# GateCircuit.net
KiCad netlist of a schematic drawn in Altium Designer
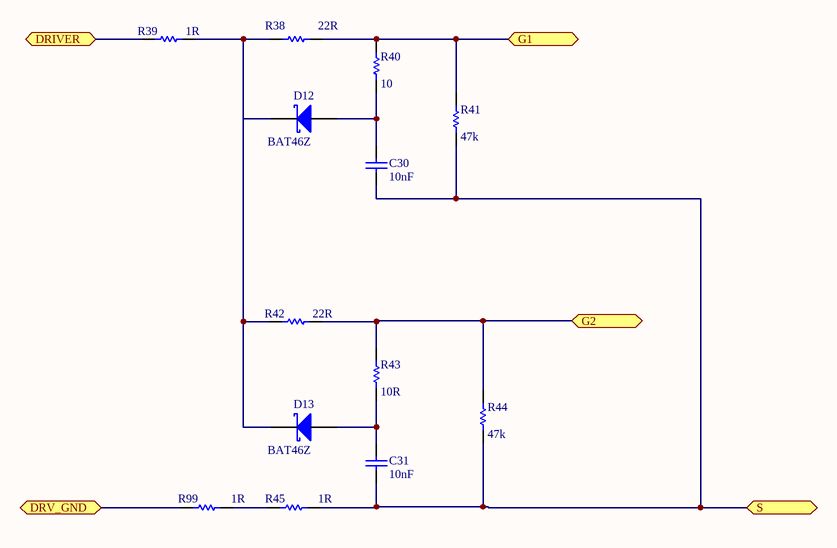
[diagram p0: GateCircuit.SchDoc]

(export (version "E")
  (design (tool "Eeschema 10.0.6"))
  (components
    (comp (ref "C30")
      (value "10nF")
      (footprint "0805_W")
      (description "Capacitor")
      (libsource (lib "Inversor_LCEE") (part "Cap_0805"))
    )
    (comp (ref "C31")
      (value "10nF")
      (footprint "0805_W")
      (description "Capacitor")
      (libsource (lib "Inversor_LCEE") (part "Cap_0805"))
    )
    (comp (ref "D12")
      (value "BAT46Z")
      (footprint "SOD-123")
      (description "Diodo Schottky")
      (libsource (lib "Sch_LCEE") (part "Schottky"))
    )
    (comp (ref "D13")
      (value "BAT46Z")
      (footprint "SOD-123")
      (description "Diodo Schottky")
      (libsource (lib "Sch_LCEE") (part "Schottky"))
    )
    (comp (ref "R38")
      (value "22R")
      (footprint "1210_W")
      (description "Resistor")
      (libsource (lib "Inversor_LCEE") (part "Res_0805"))
    )
    (comp (ref "R39")
      (value "1R")
      (footprint "0805_W")
      (description "Resistor")
      (libsource (lib "Inversor_LCEE") (part "Res_0805"))
    )
    (comp (ref "R40")
      (value "10")
      (footprint "0805_W")
      (description "Resistor")
      (libsource (lib "Inversor_LCEE") (part "Res_0805"))
    )
    (comp (ref "R41")
      (value "47k")
      (footprint "0805_W")
      (description "Resistor")
      (libsource (lib "Inversor_LCEE") (part "Res_0805"))
    )
    (comp (ref "R42")
      (value "22R")
      (footprint "1210_W")
      (description "Resistor")
      (libsource (lib "Inversor_LCEE") (part "Res_0805"))
    )
    (comp (ref "R43")
      (value "10R")
      (footprint "0805_W")
      (description "Resistor")
      (libsource (lib "Inversor_LCEE") (part "Res_0805"))
    )
    (comp (ref "R44")
      (value "47k")
      (footprint "0805_W")
      (description "Resistor")
      (libsource (lib "Inversor_LCEE") (part "Res_0805"))
    )
    (comp (ref "R45")
      (value "1R")
      (footprint "0805_W")
      (description "Resistor")
      (libsource (lib "Inversor_LCEE") (part "Res_0805"))
    )
    (comp (ref "R99")
      (value "1R")
      (footprint "0805_W")
      (description "Resistor")
      (libsource (lib "Inversor_LCEE") (part "Res_0805"))
    )
  )
  (nets
    (net (code "1") (name "/DRIVER") (class "Default")
      (node (ref "R39") (pin "2") (pinfunction "2_2") (pintype "passive"))
    )
    (net (code "2") (name "/DRV_GND") (class "Default")
      (node (ref "R99") (pin "2") (pinfunction "2_2") (pintype "passive"))
    )
    (net (code "3") (name "/G1") (class "Default")
      (node (ref "R38") (pin "1") (pinfunction "1_1") (pintype "passive"))
      (node (ref "R40") (pin "1") (pinfunction "1_1") (pintype "passive"))
      (node (ref "R41") (pin "1") (pinfunction "1_1") (pintype "passive"))
    )
    (net (code "4") (name "/G2") (class "Default")
      (node (ref "R42") (pin "1") (pinfunction "1_1") (pintype "passive"))
      (node (ref "R43") (pin "1") (pinfunction "1_1") (pintype "passive"))
      (node (ref "R44") (pin "1") (pinfunction "1_1") (pintype "passive"))
    )
    (net (code "5") (name "/S") (class "Default")
      (node (ref "C30") (pin "1") (pinfunction "1_1") (pintype "passive"))
      (node (ref "C31") (pin "1") (pinfunction "1_1") (pintype "passive"))
      (node (ref "R41") (pin "2") (pinfunction "2_2") (pintype "passive"))
      (node (ref "R44") (pin "2") (pinfunction "2_2") (pintype "passive"))
      (node (ref "R45") (pin "1") (pinfunction "1_1") (pintype "passive"))
    )
    (net (code "6") (name "Net-(D12-A)") (class "Default")
      (node (ref "C30") (pin "2") (pinfunction "2_2") (pintype "passive"))
      (node (ref "D12") (pin "1") (pinfunction "A_1") (pintype "passive"))
      (node (ref "R40") (pin "2") (pinfunction "2_2") (pintype "passive"))
    )
    (net (code "7") (name "Net-(D12-K)") (class "Default")
      (node (ref "D12") (pin "2") (pinfunction "K_2") (pintype "passive"))
      (node (ref "D13") (pin "2") (pinfunction "K_2") (pintype "passive"))
      (node (ref "R38") (pin "2") (pinfunction "2_2") (pintype "passive"))
      (node (ref "R39") (pin "1") (pinfunction "1_1") (pintype "passive"))
      (node (ref "R42") (pin "2") (pinfunction "2_2") (pintype "passive"))
    )
    (net (code "8") (name "Net-(D13-A)") (class "Default")
      (node (ref "C31") (pin "2") (pinfunction "2_2") (pintype "passive"))
      (node (ref "D13") (pin "1") (pinfunction "A_1") (pintype "passive"))
      (node (ref "R43") (pin "2") (pinfunction "2_2") (pintype "passive"))
    )
    (net (code "9") (name "Net-(R45-Pad2)") (class "Default")
      (node (ref "R45") (pin "2") (pinfunction "2_2") (pintype "passive"))
      (node (ref "R99") (pin "1") (pinfunction "1_1") (pintype "passive"))
    )
  )
)
